# powerDistribution.net
KiCad netlist of a schematic drawn in EAGLE
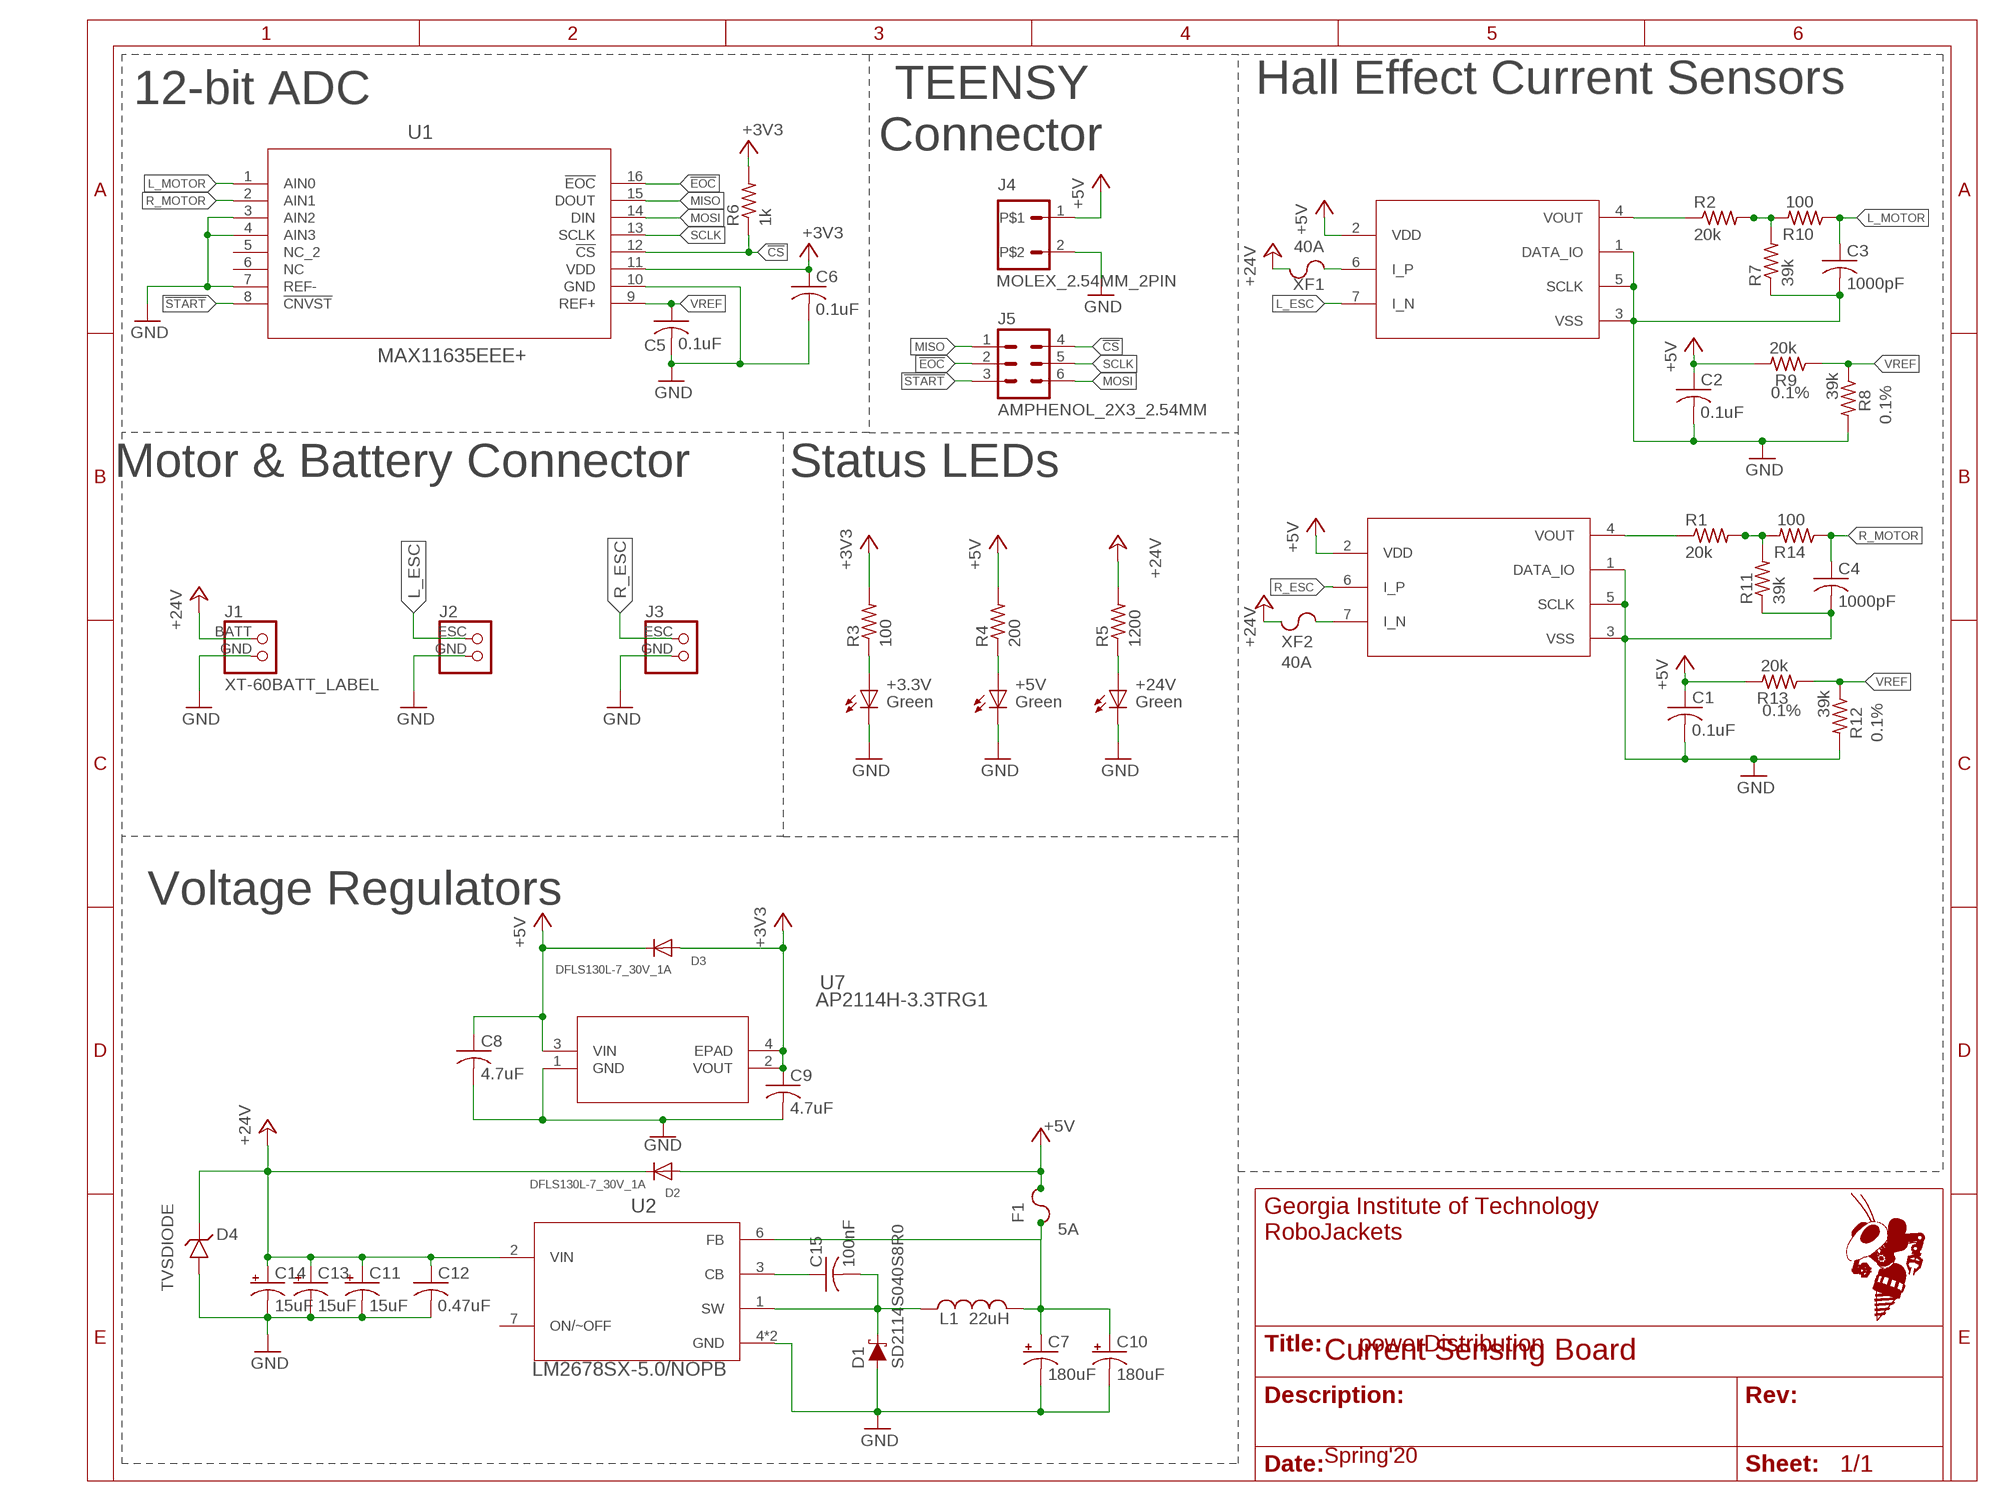
[diagram p0: schematic, sheet 1]

(export (version "E")
  (design (tool "Eeschema 10.0.6"))
  (components
    (comp (ref "+3.3V")
      (value "Green")
      (footprint "eagle-import:CHIP-LED0603")
      (libsource (lib "eagle-import") (part "LED-SMD"))
    )
    (comp (ref "+5V")
      (value "Green")
      (footprint "eagle-import:CHIP-LED0603")
      (libsource (lib "eagle-import") (part "LED-SMD"))
    )
    (comp (ref "+24V")
      (value "Green")
      (footprint "eagle-import:CHIP-LED0603")
      (libsource (lib "eagle-import") (part "LED-SMD"))
    )
    (comp (ref "C1")
      (value "0.1uF")
      (footprint "eagle-import:C0603")
      (libsource (lib "eagle-import") (part "C-USC0603"))
    )
    (comp (ref "C2")
      (value "0.1uF")
      (footprint "eagle-import:C0603")
      (libsource (lib "eagle-import") (part "C-USC0603"))
    )
    (comp (ref "C3")
      (value "1000pF")
      (footprint "eagle-import:C0603")
      (libsource (lib "eagle-import") (part "C-USC0603"))
    )
    (comp (ref "C4")
      (value "1000pF")
      (footprint "eagle-import:C0603")
      (libsource (lib "eagle-import") (part "C-USC0603"))
    )
    (comp (ref "C5")
      (value "0.1uF")
      (footprint "eagle-import:C0603")
      (libsource (lib "eagle-import") (part "C-USC0603"))
    )
    (comp (ref "C6")
      (value "0.1uF")
      (footprint "eagle-import:C0603")
      (libsource (lib "eagle-import") (part "C-USC0603"))
    )
    (comp (ref "C7")
      (value "180uF")
      (footprint "eagle-import:860010373009")
      (libsource (lib "eagle-import") (part "860010373009"))
    )
    (comp (ref "C8")
      (value "4.7uF")
      (footprint "eagle-import:C0603")
      (libsource (lib "eagle-import") (part "C-USC0603"))
    )
    (comp (ref "C9")
      (value "4.7uF")
      (footprint "eagle-import:C0603")
      (libsource (lib "eagle-import") (part "C-USC0603"))
    )
    (comp (ref "C10")
      (value "180uF")
      (footprint "eagle-import:860010373009")
      (libsource (lib "eagle-import") (part "860010373009"))
    )
    (comp (ref "C11")
      (value "15uF")
      (footprint "eagle-import:TR3E156M050C0300")
      (libsource (lib "eagle-import") (part "TR3E156M050C0300"))
    )
    (comp (ref "C12")
      (value "0.47uF")
      (footprint "eagle-import:C0603")
      (libsource (lib "eagle-import") (part "C-USC0603"))
    )
    (comp (ref "C13")
      (value "15uF")
      (footprint "eagle-import:TR3E156M050C0300")
      (libsource (lib "eagle-import") (part "TR3E156M050C0300"))
    )
    (comp (ref "C14")
      (value "15uF")
      (footprint "eagle-import:TR3E156M050C0300")
      (libsource (lib "eagle-import") (part "TR3E156M050C0300"))
    )
    (comp (ref "C15")
      (value "100nF")
      (footprint "eagle-import:C0603")
      (libsource (lib "eagle-import") (part "C-USC0603"))
    )
    (comp (ref "D1")
      (value "SD2114S040S8R0")
      (footprint "eagle-import:SD2114S040S8R0")
      (libsource (lib "eagle-import") (part "SD2114S040S8R0"))
    )
    (comp (ref "D2")
      (value "DFLS130L-7_30V_1A")
      (footprint "eagle-import:DFLS130L-7_30V_1A")
      (libsource (lib "eagle-import") (part "DFLS130L-7_30V_1A"))
    )
    (comp (ref "D3")
      (value "DFLS130L-7_30V_1A")
      (footprint "eagle-import:DFLS130L-7_30V_1A")
      (libsource (lib "eagle-import") (part "DFLS130L-7_30V_1A"))
    )
    (comp (ref "D4")
      (value "TVSDIODE")
      (footprint "eagle-import:TVSDIODE")
      (libsource (lib "eagle-import") (part "TVSDIODE"))
    )
    (comp (ref "F1")
      (value "5A")
      (footprint "eagle-import:ERB-RE5R00V")
      (libsource (lib "eagle-import") (part "ERB-RE5R00V"))
    )
    (comp (ref "J1")
      (value "XT-60BATT_LABEL")
      (footprint "eagle-import:XT-60")
      (libsource (lib "eagle-import") (part "XT-60BATT_LABEL"))
    )
    (comp (ref "J2")
      (value "CONNECTORESC_CONNECTOR")
      (footprint "eagle-import:ESC_CONNECT")
      (libsource (lib "eagle-import") (part "CONNECTORESC_CONNECTOR"))
    )
    (comp (ref "J3")
      (value "CONNECTORESC_CONNECTOR")
      (footprint "eagle-import:ESC_CONNECT")
      (libsource (lib "eagle-import") (part "CONNECTORESC_CONNECTOR"))
    )
    (comp (ref "J4")
      (value "MOLEX_2.54MM_2PIN")
      (footprint "eagle-import:MOLEX_2.54MM_2PIN")
      (libsource (lib "eagle-import") (part "MOLEX_2.54MM_2PIN"))
    )
    (comp (ref "J5")
      (value "AMPHENOL_2X3_2.54MM")
      (footprint "eagle-import:AMPHENOL_2X3_2.54MM")
      (libsource (lib "eagle-import") (part "AMPHENOL_2X3_2.54MM"))
    )
    (comp (ref "L1")
      (value "22uH")
      (footprint "eagle-import:INDUCTOR22")
      (libsource (lib "eagle-import") (part "7447709220"))
    )
    (comp (ref "R1")
      (value "20k")
      (footprint "eagle-import:R0603")
      (libsource (lib "eagle-import") (part "R-US_R0603"))
    )
    (comp (ref "R2")
      (value "20k")
      (footprint "eagle-import:R0603")
      (libsource (lib "eagle-import") (part "R-US_R0603"))
    )
    (comp (ref "R3")
      (value "100")
      (footprint "eagle-import:R0603")
      (libsource (lib "eagle-import") (part "R-US_R0603"))
    )
    (comp (ref "R4")
      (value "200")
      (footprint "eagle-import:R0603")
      (libsource (lib "eagle-import") (part "R-US_R0603"))
    )
    (comp (ref "R5")
      (value "1200")
      (footprint "eagle-import:R0603")
      (libsource (lib "eagle-import") (part "R-US_R0603"))
    )
    (comp (ref "R6")
      (value "1k")
      (footprint "eagle-import:R0603")
      (libsource (lib "eagle-import") (part "R-US_R0603"))
    )
    (comp (ref "R7")
      (value "39k")
      (footprint "eagle-import:R0603")
      (libsource (lib "eagle-import") (part "R-US_R0603"))
    )
    (comp (ref "R8")
      (value "39k")
      (footprint "eagle-import:R0603")
      (libsource (lib "eagle-import") (part "R-US_R0603"))
    )
    (comp (ref "R9")
      (value "20k")
      (footprint "eagle-import:R0603")
      (libsource (lib "eagle-import") (part "R-US_R0603"))
    )
    (comp (ref "R10")
      (value "100")
      (footprint "eagle-import:R0603")
      (libsource (lib "eagle-import") (part "R-US_R0603"))
    )
    (comp (ref "R11")
      (value "39k")
      (footprint "eagle-import:R0603")
      (libsource (lib "eagle-import") (part "R-US_R0603"))
    )
    (comp (ref "R12")
      (value "39k")
      (footprint "eagle-import:R0603")
      (libsource (lib "eagle-import") (part "R-US_R0603"))
    )
    (comp (ref "R13")
      (value "20k")
      (footprint "eagle-import:R0603")
      (libsource (lib "eagle-import") (part "R-US_R0603"))
    )
    (comp (ref "R14")
      (value "100")
      (footprint "eagle-import:R0603")
      (libsource (lib "eagle-import") (part "R-US_R0603"))
    )
    (comp (ref "U1")
      (value "MAX11635EEE+")
      (footprint "eagle-import:21-0055H_16_MXM")
      (libsource (lib "eagle-import") (part "MAX11635EEE+"))
    )
    (comp (ref "U2")
      (value "LM2678SX-5.0/NOPB")
      (footprint "eagle-import:TS7B")
      (libsource (lib "eagle-import") (part "LM2678SX-5.0/NOPB"))
    )
    (comp (ref "U3")
      (value "CQ2065")
      (footprint "eagle-import:974-1092-1")
      (libsource (lib "eagle-import") (part "CQ2065"))
    )
    (comp (ref "U4")
      (value "CQ2065")
      (footprint "eagle-import:974-1092-1")
      (libsource (lib "eagle-import") (part "CQ2065"))
    )
    (comp (ref "U7")
      (value "AP2114H-3.3TRG1")
      (footprint "eagle-import:SOT-223")
      (fields (field (name "MANUFACTURER_PART_NUMBER") "AP2114H3.3TRG1"))
      (libsource (lib "eagle-import") (part "AP2114H-3.3TRG1"))
    )
    (comp (ref "XF1")
      (value "40A")
      (footprint "eagle-import:3550")
      (libsource (lib "eagle-import") (part "3550(2)"))
    )
    (comp (ref "XF2")
      (value "40A")
      (footprint "eagle-import:3550")
      (libsource (lib "eagle-import") (part "3550(2)"))
    )
  )
  (nets
    (net (code "1") (name "+3V3") (class "Default")
      (node (ref "C6") (pin "1") (pinfunction "1_1") (pintype "passive"))
      (node (ref "C9") (pin "1") (pinfunction "1_1") (pintype "passive"))
      (node (ref "D3") (pin "P$2") (pinfunction "A_P$2") (pintype "passive"))
      (node (ref "R3") (pin "2") (pinfunction "2_2") (pintype "passive"))
      (node (ref "R6") (pin "2") (pinfunction "2_2") (pintype "passive"))
      (node (ref "U1") (pin "11") (pinfunction "VDD_11") (pintype "power_in"))
      (node (ref "U7") (pin "2") (pinfunction "VOUT_2") (pintype "output"))
      (node (ref "U7") (pin "4") (pinfunction "EPAD_4") (pintype "passive"))
    )
    (net (code "2") (name "+5V") (class "Default")
      (node (ref "C1") (pin "1") (pinfunction "1_1") (pintype "passive"))
      (node (ref "C2") (pin "1") (pinfunction "1_1") (pintype "passive"))
      (node (ref "C8") (pin "1") (pinfunction "1_1") (pintype "passive"))
      (node (ref "D2") (pin "P$2") (pinfunction "A_P$2") (pintype "passive"))
      (node (ref "D3") (pin "P$1") (pinfunction "C_P$1") (pintype "passive"))
      (node (ref "F1") (pin "2") (pinfunction "2_2") (pintype "bidirectional"))
      (node (ref "J4") (pin "1") (pinfunction "P$1_1") (pintype "bidirectional"))
      (node (ref "R13") (pin "2") (pinfunction "2_2") (pintype "passive"))
      (node (ref "R4") (pin "2") (pinfunction "2_2") (pintype "passive"))
      (node (ref "R9") (pin "2") (pinfunction "2_2") (pintype "passive"))
      (node (ref "U3") (pin "2") (pinfunction "VDD_2") (pintype "bidirectional"))
      (node (ref "U4") (pin "2") (pinfunction "VDD_2") (pintype "bidirectional"))
      (node (ref "U7") (pin "3") (pinfunction "VIN_3") (pintype "input"))
    )
    (net (code "3") (name "+24V") (class "Default")
      (node (ref "C11") (pin "1") (pinfunction "+_1") (pintype "passive"))
      (node (ref "C12") (pin "1") (pinfunction "1_1") (pintype "passive"))
      (node (ref "C13") (pin "1") (pinfunction "+_1") (pintype "passive"))
      (node (ref "C14") (pin "1") (pinfunction "+_1") (pintype "passive"))
      (node (ref "D2") (pin "P$1") (pinfunction "C_P$1") (pintype "passive"))
      (node (ref "D4") (pin "P$2") (pinfunction "C_P$2") (pintype "passive"))
      (node (ref "J1") (pin "BATT") (pinfunction "1_BATT") (pintype "passive"))
      (node (ref "R5") (pin "2") (pinfunction "2_2") (pintype "passive"))
      (node (ref "U2") (pin "2") (pinfunction "VIN_2") (pintype "input"))
      (node (ref "XF1") (pin "3") (pinfunction "2_3") (pintype "bidirectional"))
      (node (ref "XF1") (pin "4") (pinfunction "2_4") (pintype "bidirectional"))
      (node (ref "XF2") (pin "1") (pinfunction "1_1") (pintype "bidirectional"))
      (node (ref "XF2") (pin "2") (pinfunction "1_2") (pintype "bidirectional"))
    )
    (net (code "4") (name "/~{CS}") (class "Default")
      (node (ref "J5") (pin "4") (pinfunction "5_4") (pintype "passive"))
      (node (ref "R6") (pin "1") (pinfunction "1_1") (pintype "passive"))
      (node (ref "U1") (pin "12") (pinfunction "~{CS}_12") (pintype "passive"))
    )
    (net (code "5") (name "/~{EOC}") (class "Default")
      (node (ref "J5") (pin "2") (pinfunction "4_2") (pintype "passive"))
      (node (ref "U1") (pin "16") (pinfunction "~{EOC}_16") (pintype "passive"))
    )
    (net (code "6") (name "/~{START}") (class "Default")
      (node (ref "J5") (pin "3") (pinfunction "2_3") (pintype "passive"))
      (node (ref "U1") (pin "8") (pinfunction "~{CNVST}_8") (pintype "passive"))
    )
    (net (code "7") (name "GND") (class "Default")
      (node (ref "+24V") (pin "C") (pinfunction "K_C") (pintype "passive"))
      (node (ref "+3.3V") (pin "C") (pinfunction "K_C") (pintype "passive"))
      (node (ref "+5V") (pin "C") (pinfunction "K_C") (pintype "passive"))
      (node (ref "C1") (pin "2") (pinfunction "2_2") (pintype "passive"))
      (node (ref "C10") (pin "2") (pinfunction "-_2") (pintype "passive"))
      (node (ref "C11") (pin "2") (pinfunction "-_2") (pintype "passive"))
      (node (ref "C12") (pin "2") (pinfunction "2_2") (pintype "passive"))
      (node (ref "C13") (pin "2") (pinfunction "-_2") (pintype "passive"))
      (node (ref "C14") (pin "2") (pinfunction "-_2") (pintype "passive"))
      (node (ref "C2") (pin "2") (pinfunction "2_2") (pintype "passive"))
      (node (ref "C3") (pin "2") (pinfunction "2_2") (pintype "passive"))
      (node (ref "C4") (pin "2") (pinfunction "2_2") (pintype "passive"))
      (node (ref "C5") (pin "2") (pinfunction "2_2") (pintype "passive"))
      (node (ref "C6") (pin "2") (pinfunction "2_2") (pintype "passive"))
      (node (ref "C7") (pin "2") (pinfunction "-_2") (pintype "passive"))
      (node (ref "C8") (pin "2") (pinfunction "2_2") (pintype "passive"))
      (node (ref "C9") (pin "2") (pinfunction "2_2") (pintype "passive"))
      (node (ref "D1") (pin "1") (pinfunction "A_1") (pintype "passive"))
      (node (ref "D4") (pin "P$1") (pinfunction "A_P$1") (pintype "passive"))
      (node (ref "J1") (pin "GND") (pinfunction "2_GND") (pintype "passive"))
      (node (ref "J2") (pin "GND") (pinfunction "2_GND") (pintype "passive"))
      (node (ref "J3") (pin "GND") (pinfunction "2_GND") (pintype "passive"))
      (node (ref "J4") (pin "2") (pinfunction "P$2_2") (pintype "bidirectional"))
      (node (ref "R11") (pin "1") (pinfunction "1_1") (pintype "passive"))
      (node (ref "R12") (pin "2") (pinfunction "2_2") (pintype "passive"))
      (node (ref "R7") (pin "1") (pinfunction "1_1") (pintype "passive"))
      (node (ref "R8") (pin "2") (pinfunction "2_2") (pintype "passive"))
      (node (ref "U1") (pin "10") (pinfunction "GND_10") (pintype "power_in"))
      (node (ref "U1") (pin "3") (pinfunction "AIN2_3") (pintype "input"))
      (node (ref "U1") (pin "4") (pinfunction "AIN3_4") (pintype "input"))
      (node (ref "U1") (pin "7") (pinfunction "REF-_7") (pintype "passive"))
      (node (ref "U2") (pin "4") (pinfunction "GND_4") (pintype "passive"))
      (node (ref "U2") (pin "8") (pinfunction "GND_8") (pintype "passive"))
      (node (ref "U3") (pin "1") (pinfunction "DATA_IO_1") (pintype "bidirectional"))
      (node (ref "U3") (pin "3") (pinfunction "VSS_3") (pintype "bidirectional"))
      (node (ref "U3") (pin "5") (pinfunction "SCLK_5") (pintype "bidirectional"))
      (node (ref "U4") (pin "1") (pinfunction "DATA_IO_1") (pintype "bidirectional"))
      (node (ref "U4") (pin "3") (pinfunction "VSS_3") (pintype "bidirectional"))
      (node (ref "U4") (pin "5") (pinfunction "SCLK_5") (pintype "bidirectional"))
      (node (ref "U7") (pin "1") (pinfunction "GND_1") (pintype "power_in"))
    )
    (net (code "8") (name "L_ESC") (class "Default")
      (node (ref "J2") (pin "ESC") (pinfunction "1_ESC") (pintype "passive"))
      (node (ref "U3") (pin "7") (pinfunction "I_N_7") (pintype "bidirectional"))
    )
    (net (code "9") (name "L_MOTOR") (class "Default")
      (node (ref "C3") (pin "1") (pinfunction "1_1") (pintype "passive"))
      (node (ref "R10") (pin "1") (pinfunction "1_1") (pintype "passive"))
      (node (ref "U1") (pin "1") (pinfunction "AIN0_1") (pintype "input"))
    )
    (net (code "10") (name "MISO") (class "Default")
      (node (ref "J5") (pin "1") (pinfunction "6_1") (pintype "passive"))
      (node (ref "U1") (pin "15") (pinfunction "DOUT_15") (pintype "output"))
    )
    (net (code "11") (name "MOSI") (class "Default")
      (node (ref "J5") (pin "6") (pinfunction "1_6") (pintype "passive"))
      (node (ref "U1") (pin "14") (pinfunction "DIN_14") (pintype "input"))
    )
    (net (code "12") (name "Net-(+3.3V-PadA)") (class "Default")
      (node (ref "+3.3V") (pin "A") (pinfunction "A_A") (pintype "passive"))
      (node (ref "R3") (pin "1") (pinfunction "1_1") (pintype "passive"))
    )
    (net (code "13") (name "Net-(+5V-PadA)") (class "Default")
      (node (ref "+5V") (pin "A") (pinfunction "A_A") (pintype "passive"))
      (node (ref "R4") (pin "1") (pinfunction "1_1") (pintype "passive"))
    )
    (net (code "14") (name "Net-(+24V-PadA)") (class "Default")
      (node (ref "+24V") (pin "A") (pinfunction "A_A") (pintype "passive"))
      (node (ref "R5") (pin "1") (pinfunction "1_1") (pintype "passive"))
    )
    (net (code "15") (name "Net-(C10-+)") (class "Default")
      (node (ref "C10") (pin "1") (pinfunction "+_1") (pintype "passive"))
      (node (ref "C7") (pin "1") (pinfunction "+_1") (pintype "passive"))
      (node (ref "F1") (pin "1") (pinfunction "1_1") (pintype "bidirectional"))
      (node (ref "L1") (pin "2") (pinfunction "2_2") (pintype "passive"))
      (node (ref "U2") (pin "6") (pinfunction "FB_6") (pintype "passive"))
    )
    (net (code "16") (name "Net-(D1-C)") (class "Default")
      (node (ref "C15") (pin "2") (pinfunction "2_2") (pintype "passive"))
      (node (ref "D1") (pin "2") (pinfunction "C_2") (pintype "passive"))
      (node (ref "L1") (pin "1") (pinfunction "1_1") (pintype "passive"))
      (node (ref "U2") (pin "1") (pinfunction "SW_1") (pintype "output"))
    )
    (net (code "17") (name "Net-(R1-Pad2)") (class "Default")
      (node (ref "R1") (pin "2") (pinfunction "2_2") (pintype "passive"))
      (node (ref "R11") (pin "2") (pinfunction "2_2") (pintype "passive"))
      (node (ref "R14") (pin "2") (pinfunction "2_2") (pintype "passive"))
    )
    (net (code "18") (name "Net-(R10-Pad2)") (class "Default")
      (node (ref "R10") (pin "2") (pinfunction "2_2") (pintype "passive"))
      (node (ref "R2") (pin "2") (pinfunction "2_2") (pintype "passive"))
      (node (ref "R7") (pin "2") (pinfunction "2_2") (pintype "passive"))
    )
    (net (code "19") (name "Net-(U2-CB)") (class "Default")
      (node (ref "C15") (pin "1") (pinfunction "1_1") (pintype "passive"))
      (node (ref "U2") (pin "3") (pinfunction "CB_3") (pintype "passive"))
    )
    (net (code "20") (name "Net-(U3-I_P)") (class "Default")
      (node (ref "U3") (pin "6") (pinfunction "I_P_6") (pintype "bidirectional"))
      (node (ref "XF1") (pin "1") (pinfunction "1_1") (pintype "bidirectional"))
      (node (ref "XF1") (pin "2") (pinfunction "1_2") (pintype "bidirectional"))
    )
    (net (code "21") (name "Net-(U3-VOUT)") (class "Default")
      (node (ref "R2") (pin "1") (pinfunction "1_1") (pintype "passive"))
      (node (ref "U3") (pin "4") (pinfunction "VOUT_4") (pintype "bidirectional"))
    )
    (net (code "22") (name "Net-(U4-I_N)") (class "Default")
      (node (ref "U4") (pin "7") (pinfunction "I_N_7") (pintype "bidirectional"))
      (node (ref "XF2") (pin "3") (pinfunction "2_3") (pintype "bidirectional"))
      (node (ref "XF2") (pin "4") (pinfunction "2_4") (pintype "bidirectional"))
    )
    (net (code "23") (name "Net-(U4-VOUT)") (class "Default")
      (node (ref "R1") (pin "1") (pinfunction "1_1") (pintype "passive"))
      (node (ref "U4") (pin "4") (pinfunction "VOUT_4") (pintype "bidirectional"))
    )
    (net (code "24") (name "R_ESC") (class "Default")
      (node (ref "J3") (pin "ESC") (pinfunction "1_ESC") (pintype "passive"))
      (node (ref "U4") (pin "6") (pinfunction "I_P_6") (pintype "bidirectional"))
    )
    (net (code "25") (name "R_MOTOR") (class "Default")
      (node (ref "C4") (pin "1") (pinfunction "1_1") (pintype "passive"))
      (node (ref "R14") (pin "1") (pinfunction "1_1") (pintype "passive"))
      (node (ref "U1") (pin "2") (pinfunction "AIN1_2") (pintype "input"))
    )
    (net (code "26") (name "SCLK") (class "Default")
      (node (ref "J5") (pin "5") (pinfunction "3_5") (pintype "passive"))
      (node (ref "U1") (pin "13") (pinfunction "SCLK_13") (pintype "passive"))
    )
    (net (code "27") (name "VREF") (class "Default")
      (node (ref "C5") (pin "1") (pinfunction "1_1") (pintype "passive"))
      (node (ref "R12") (pin "1") (pinfunction "1_1") (pintype "passive"))
      (node (ref "R13") (pin "1") (pinfunction "1_1") (pintype "passive"))
      (node (ref "R8") (pin "1") (pinfunction "1_1") (pintype "passive"))
      (node (ref "R9") (pin "1") (pinfunction "1_1") (pintype "passive"))
      (node (ref "U1") (pin "9") (pinfunction "REF+_9") (pintype "passive"))
    )
    (net (code "28") (name "unconnected-(U1-NC-Pad6)") (class "Default")
      (node (ref "U1") (pin "6") (pinfunction "NC_6") (pintype "no_connect"))
    )
    (net (code "29") (name "unconnected-(U1-NC_2-Pad5)") (class "Default")
      (node (ref "U1") (pin "5") (pinfunction "NC_2_5") (pintype "no_connect"))
    )
    (net (code "30") (name "unconnected-(U2-ON{slash}~{OFF}-Pad7)") (class "Default")
      (node (ref "U2") (pin "7") (pinfunction "ON/~{OFF}_7") (pintype "passive"))
    )
  )
)
